# LIS3DH.net
KiCad netlist of a schematic drawn in Altium Designer
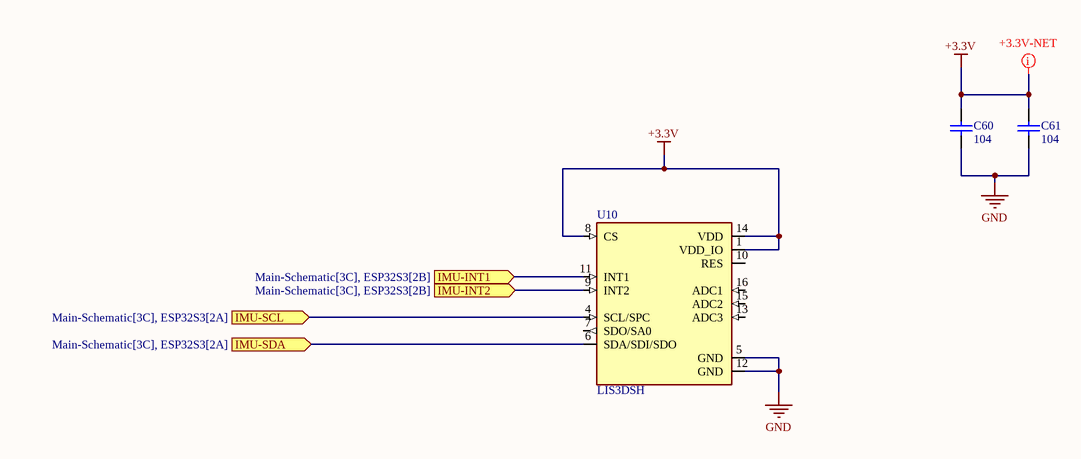
[diagram p0: LIS3DH.SchDoc]

(export (version "E")
  (design (tool "Eeschema 10.0.6"))
  (components
    (comp (ref "C60")
      (value "104")
      (footprint "CAP_0603")
      (description "Non-polarized capacitor")
      (libsource (lib "Capacitor") (part "Cap_NP"))
    )
    (comp (ref "C61")
      (value "104")
      (footprint "CAP_0603")
      (description "Non-polarized capacitor")
      (libsource (lib "Capacitor") (part "Cap_NP"))
    )
    (comp (ref "U10")
      (value "LIS3DSH")
      (footprint "LGA16R50P5X3_300X300X100N")
      (description "Accelerometer X, Y, Z Axis Â±2g, 4g, 6g, 8g, 16g 1.56Hz ~ 800Hz 16-LGA _3x3_")
      (fields (field (name "MF") "STMicroelectronics"))
      (libsource (lib "LIS3DSH") (part "LIS3DSH"))
    )
  )
  (nets
    (net (code "1") (name "+3.3V") (class "Default")
      (node (ref "C60") (pin "2") (pinfunction "2_2") (pintype "passive"))
      (node (ref "C61") (pin "2") (pinfunction "2_2") (pintype "passive"))
      (node (ref "U10") (pin "1") (pinfunction "VDD_IO_1") (pintype "power_in"))
      (node (ref "U10") (pin "14") (pinfunction "VDD_14") (pintype "power_in"))
      (node (ref "U10") (pin "8") (pinfunction "CS_8") (pintype "input"))
    )
    (net (code "2") (name "/IMU-INT1") (class "Default")
      (node (ref "U10") (pin "11") (pinfunction "INT1_11") (pintype "input"))
    )
    (net (code "3") (name "/IMU-INT2") (class "Default")
      (node (ref "U10") (pin "9") (pinfunction "INT2_9") (pintype "input"))
    )
    (net (code "4") (name "/IMU-SCL") (class "Default")
      (node (ref "U10") (pin "4") (pinfunction "SCL/SPC_4") (pintype "input"))
    )
    (net (code "5") (name "/IMU-SDA") (class "Default")
      (node (ref "U10") (pin "6") (pinfunction "SDA/SDI/SDO_6") (pintype "bidirectional"))
    )
    (net (code "6") (name "GND") (class "Default")
      (node (ref "C60") (pin "1") (pinfunction "1_1") (pintype "passive"))
      (node (ref "C61") (pin "1") (pinfunction "1_1") (pintype "passive"))
      (node (ref "U10") (pin "12") (pinfunction "GND_12") (pintype "power_in"))
      (node (ref "U10") (pin "5") (pinfunction "GND_5") (pintype "power_in"))
    )
    (net (code "7") (name "unconnected-(U10-ADC1-Pad16)") (class "Default")
      (node (ref "U10") (pin "16") (pinfunction "ADC1_16") (pintype "input"))
    )
    (net (code "8") (name "unconnected-(U10-ADC2-Pad15)") (class "Default")
      (node (ref "U10") (pin "15") (pinfunction "ADC2_15") (pintype "input"))
    )
    (net (code "9") (name "unconnected-(U10-ADC3-Pad13)") (class "Default")
      (node (ref "U10") (pin "13") (pinfunction "ADC3_13") (pintype "input"))
    )
    (net (code "10") (name "unconnected-(U10-RES-Pad10)") (class "Default")
      (node (ref "U10") (pin "10") (pinfunction "RES_10") (pintype "power_in"))
    )
    (net (code "11") (name "unconnected-(U10-SDO{slash}SA0-Pad7)") (class "Default")
      (node (ref "U10") (pin "7") (pinfunction "SDO/SA0_7") (pintype "output"))
    )
  )
)
